# 6502_Based_Board.net
KiCad netlist of a schematic drawn in EAGLE
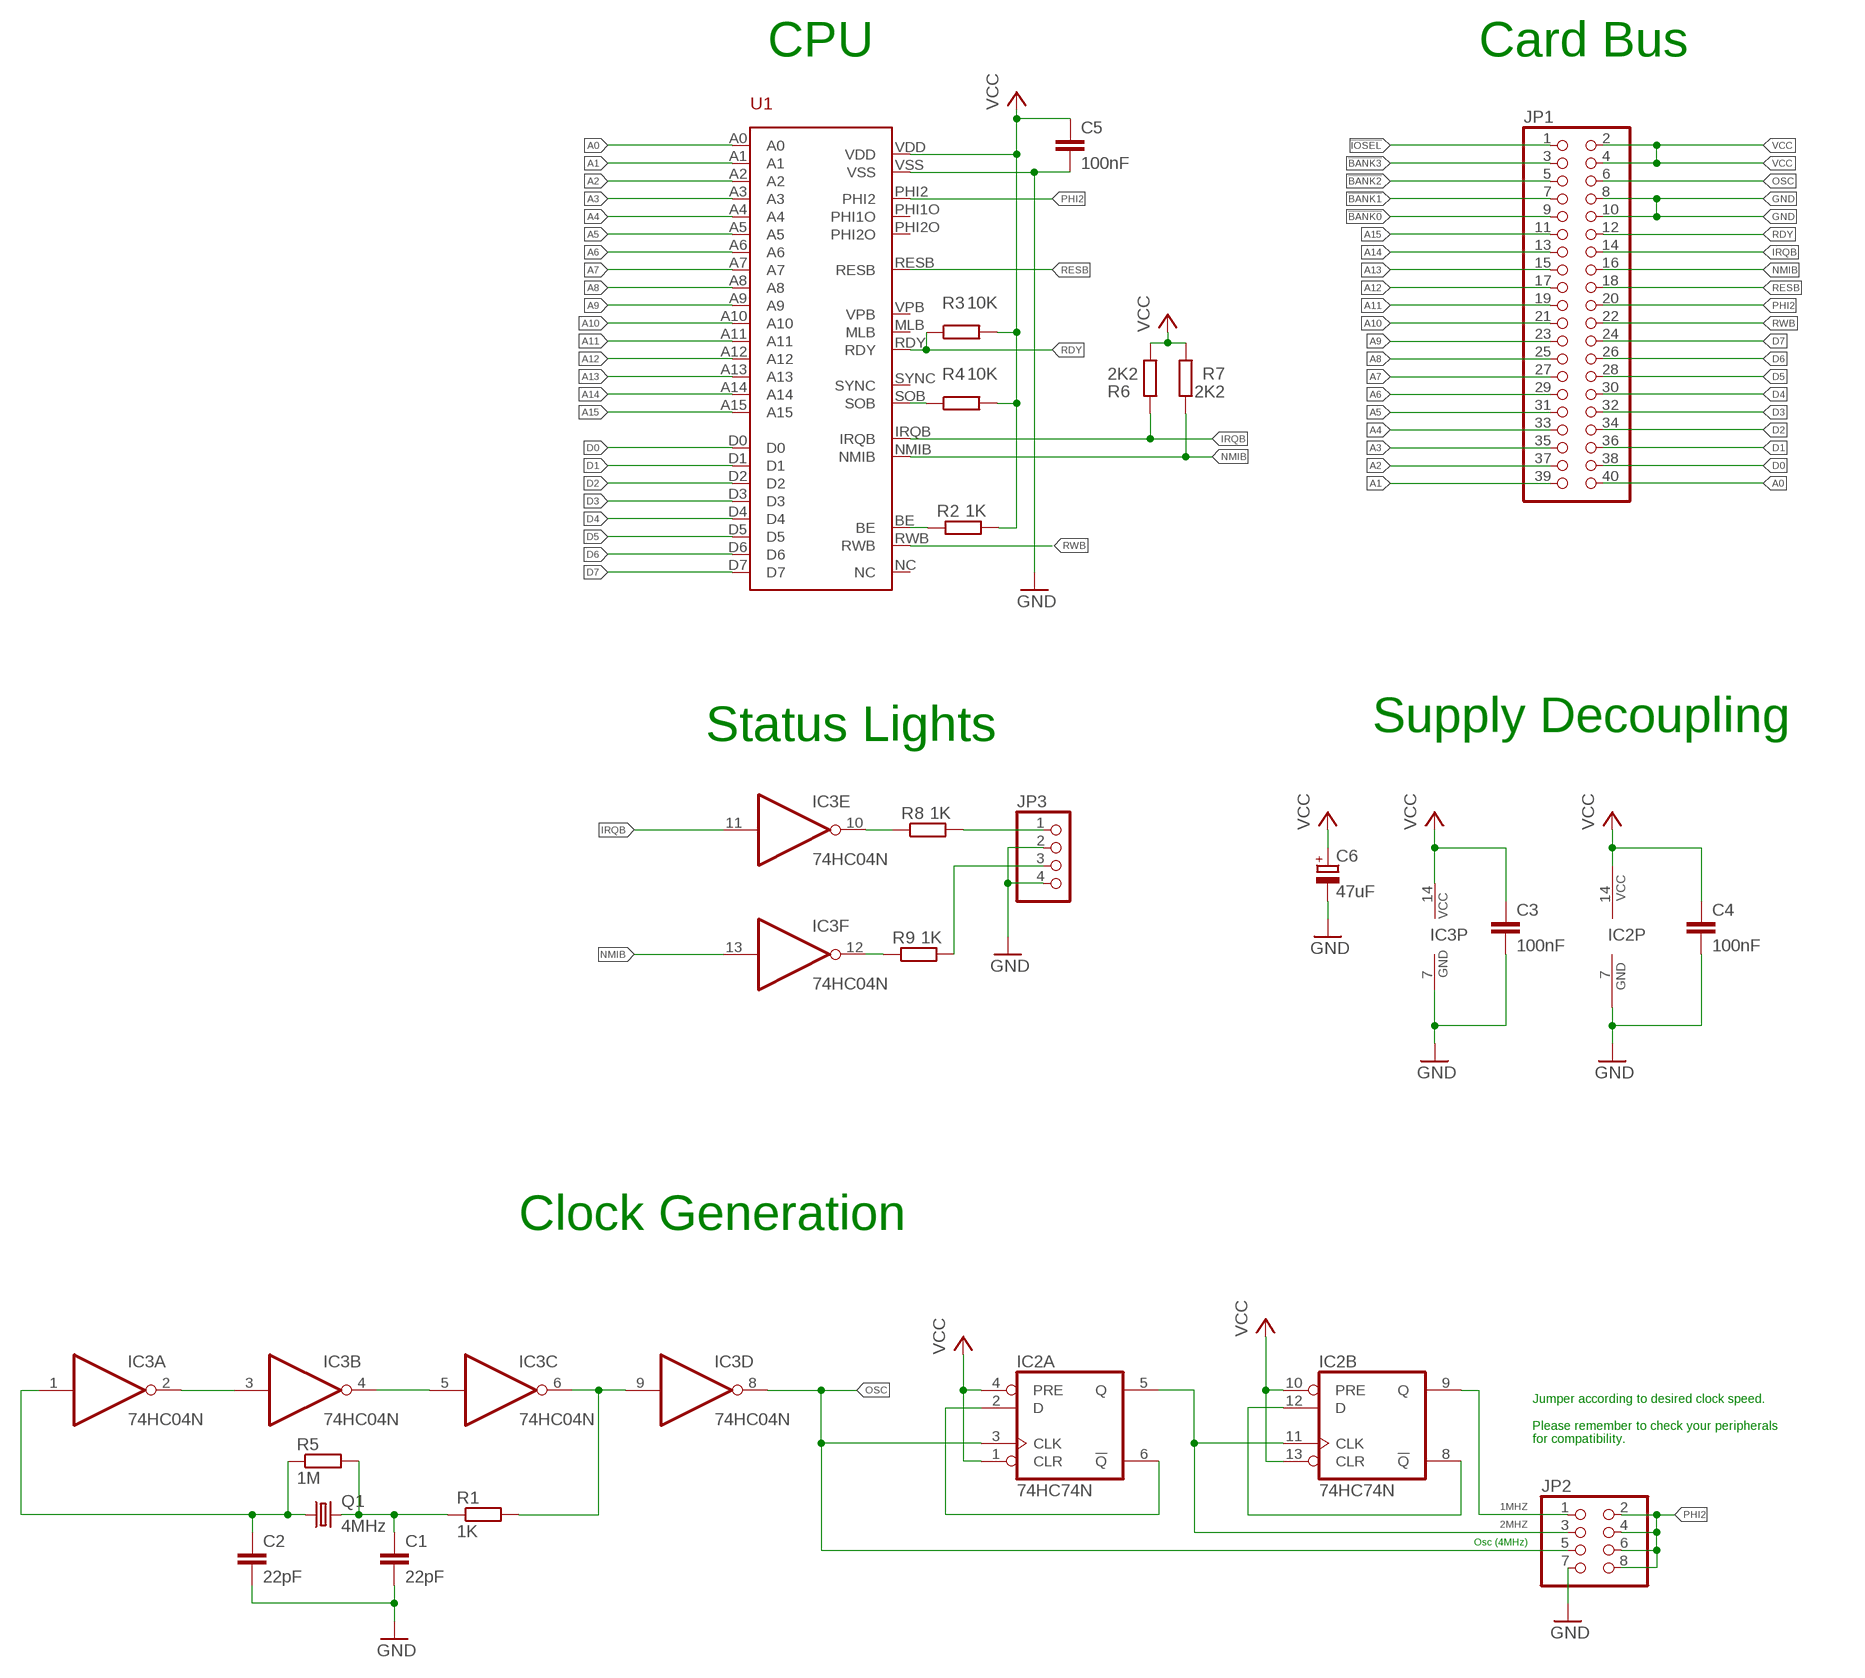
[diagram p0: schematic, sheet 1]

(export (version "E")
  (design (tool "Eeschema 10.0.6"))
  (components
    (comp (ref "C1")
      (value "22pF")
      (footprint "eagle-import:C050-025X075")
      (libsource (lib "eagle-import") (part "C-EU050-025X075"))
    )
    (comp (ref "C2")
      (value "22pF")
      (footprint "eagle-import:C050-025X075")
      (libsource (lib "eagle-import") (part "C-EU050-025X075"))
    )
    (comp (ref "C3")
      (value "100nF")
      (footprint "eagle-import:C050-025X075")
      (libsource (lib "eagle-import") (part "C-EU050-025X075"))
    )
    (comp (ref "C4")
      (value "100nF")
      (footprint "eagle-import:C050-025X075")
      (libsource (lib "eagle-import") (part "C-EU050-025X075"))
    )
    (comp (ref "C5")
      (value "100nF")
      (footprint "eagle-import:C050-025X075")
      (libsource (lib "eagle-import") (part "C-EU050-025X075"))
    )
    (comp (ref "C6")
      (value "47uF")
      (footprint "eagle-import:E2,5-7")
      (libsource (lib "eagle-import") (part "CPOL-EUE2.5-7"))
    )
    (comp (ref "IC2")
      (value "74HC74N")
      (footprint "eagle-import:DIL14")
      (libsource (lib "eagle-import") (part "7474NLS"))
    )
    (comp (ref "IC3")
      (value "74HC04N")
      (footprint "eagle-import:DIL14")
      (libsource (lib "eagle-import") (part "7404NHC"))
    )
    (comp (ref "JP1")
      (value "PINHD-2X20/90")
      (footprint "eagle-import:2X20_90")
      (libsource (lib "eagle-import") (part "PINHD-2X20/90"))
    )
    (comp (ref "JP2")
      (value "PINHD-2X4")
      (footprint "eagle-import:2X04")
      (libsource (lib "eagle-import") (part "PINHD-2X4"))
    )
    (comp (ref "JP3")
      (value "PINHD-1X4/90")
      (footprint "eagle-import:1X04_90")
      (libsource (lib "eagle-import") (part "PINHD-1X4/90"))
    )
    (comp (ref "Q1")
      (value "4MHz")
      (footprint "eagle-import:HC49_S")
      (libsource (lib "eagle-import") (part "CRYSTALHC49S"))
    )
    (comp (ref "R1")
      (value "1K")
      (footprint "eagle-import:0207_2V")
      (libsource (lib "eagle-import") (part "R-EU_0207/2V"))
    )
    (comp (ref "R2")
      (value "1K")
      (footprint "eagle-import:0207_2V")
      (libsource (lib "eagle-import") (part "R-EU_0207/2V"))
    )
    (comp (ref "R3")
      (value "10K")
      (footprint "eagle-import:0207_2V")
      (libsource (lib "eagle-import") (part "R-EU_0207/2V"))
    )
    (comp (ref "R4")
      (value "10K")
      (footprint "eagle-import:0207_2V")
      (libsource (lib "eagle-import") (part "R-EU_0207/2V"))
    )
    (comp (ref "R5")
      (value "1M")
      (footprint "eagle-import:0207_2V")
      (libsource (lib "eagle-import") (part "R-EU_0207/2V"))
    )
    (comp (ref "R6")
      (value "2K2")
      (footprint "eagle-import:0207_10")
      (libsource (lib "eagle-import") (part "R-EU_0207/10"))
    )
    (comp (ref "R7")
      (value "2K2")
      (footprint "eagle-import:0207_10")
      (libsource (lib "eagle-import") (part "R-EU_0207/10"))
    )
    (comp (ref "R8")
      (value "1K")
      (footprint "eagle-import:0207_2V")
      (libsource (lib "eagle-import") (part "R-EU_0207/2V"))
    )
    (comp (ref "R9")
      (value "1K")
      (footprint "eagle-import:0207_2V")
      (libsource (lib "eagle-import") (part "R-EU_0207/2V"))
    )
    (comp (ref "U1")
      (value "W65C02S-DIP")
      (footprint "eagle-import:DIP40")
      (libsource (lib "eagle-import") (part "W65C02S-DIP"))
    )
  )
  (nets
    (net (code "1") (name "/1MHZ") (class "Default")
      (node (ref "IC2") (pin "9") (pinfunction "Q_9") (pintype "output"))
      (node (ref "JP2") (pin "1") (pinfunction "1_1") (pintype "passive"))
    )
    (net (code "2") (name "/2MHZ") (class "Default")
      (node (ref "IC2") (pin "11") (pinfunction "CLK_11") (pintype "input"))
      (node (ref "IC2") (pin "5") (pinfunction "Q_5") (pintype "output"))
      (node (ref "JP2") (pin "3") (pinfunction "3_3") (pintype "passive"))
    )
    (net (code "3") (name "/~{BANK0}") (class "Default")
      (node (ref "JP1") (pin "9") (pinfunction "9_9") (pintype "passive"))
    )
    (net (code "4") (name "/~{BANK1}") (class "Default")
      (node (ref "JP1") (pin "7") (pinfunction "7_7") (pintype "passive"))
    )
    (net (code "5") (name "/~{BANK2}") (class "Default")
      (node (ref "JP1") (pin "5") (pinfunction "5_5") (pintype "passive"))
    )
    (net (code "6") (name "/~{BANK3}") (class "Default")
      (node (ref "JP1") (pin "3") (pinfunction "3_3") (pintype "passive"))
    )
    (net (code "7") (name "/~{IOSEL}") (class "Default")
      (node (ref "JP1") (pin "1") (pinfunction "1_1") (pintype "passive"))
    )
    (net (code "8") (name "A0") (class "Default")
      (node (ref "JP1") (pin "40") (pinfunction "40_40") (pintype "passive"))
      (node (ref "U1") (pin "A0") (pinfunction "A0_A0") (pintype "output"))
    )
    (net (code "9") (name "A1") (class "Default")
      (node (ref "JP1") (pin "39") (pinfunction "39_39") (pintype "passive"))
      (node (ref "U1") (pin "A1") (pinfunction "A1_A1") (pintype "output"))
    )
    (net (code "10") (name "A2") (class "Default")
      (node (ref "JP1") (pin "37") (pinfunction "37_37") (pintype "passive"))
      (node (ref "U1") (pin "A2") (pinfunction "A2_A2") (pintype "output"))
    )
    (net (code "11") (name "A3") (class "Default")
      (node (ref "JP1") (pin "35") (pinfunction "35_35") (pintype "passive"))
      (node (ref "U1") (pin "A3") (pinfunction "A3_A3") (pintype "output"))
    )
    (net (code "12") (name "A4") (class "Default")
      (node (ref "JP1") (pin "33") (pinfunction "33_33") (pintype "passive"))
      (node (ref "U1") (pin "A4") (pinfunction "A4_A4") (pintype "output"))
    )
    (net (code "13") (name "A5") (class "Default")
      (node (ref "JP1") (pin "31") (pinfunction "31_31") (pintype "passive"))
      (node (ref "U1") (pin "A5") (pinfunction "A5_A5") (pintype "output"))
    )
    (net (code "14") (name "A6") (class "Default")
      (node (ref "JP1") (pin "29") (pinfunction "29_29") (pintype "passive"))
      (node (ref "U1") (pin "A6") (pinfunction "A6_A6") (pintype "output"))
    )
    (net (code "15") (name "A7") (class "Default")
      (node (ref "JP1") (pin "27") (pinfunction "27_27") (pintype "passive"))
      (node (ref "U1") (pin "A7") (pinfunction "A7_A7") (pintype "output"))
    )
    (net (code "16") (name "A8") (class "Default")
      (node (ref "JP1") (pin "25") (pinfunction "25_25") (pintype "passive"))
      (node (ref "U1") (pin "A8") (pinfunction "A8_A8") (pintype "output"))
    )
    (net (code "17") (name "A9") (class "Default")
      (node (ref "JP1") (pin "23") (pinfunction "23_23") (pintype "passive"))
      (node (ref "U1") (pin "A9") (pinfunction "A9_A9") (pintype "output"))
    )
    (net (code "18") (name "A10") (class "Default")
      (node (ref "JP1") (pin "21") (pinfunction "21_21") (pintype "passive"))
      (node (ref "U1") (pin "A10") (pinfunction "A10_A10") (pintype "output"))
    )
    (net (code "19") (name "A11") (class "Default")
      (node (ref "JP1") (pin "19") (pinfunction "19_19") (pintype "passive"))
      (node (ref "U1") (pin "A11") (pinfunction "A11_A11") (pintype "output"))
    )
    (net (code "20") (name "A12") (class "Default")
      (node (ref "JP1") (pin "17") (pinfunction "17_17") (pintype "passive"))
      (node (ref "U1") (pin "A12") (pinfunction "A12_A12") (pintype "output"))
    )
    (net (code "21") (name "A13") (class "Default")
      (node (ref "JP1") (pin "15") (pinfunction "15_15") (pintype "passive"))
      (node (ref "U1") (pin "A13") (pinfunction "A13_A13") (pintype "output"))
    )
    (net (code "22") (name "A14") (class "Default")
      (node (ref "JP1") (pin "13") (pinfunction "13_13") (pintype "passive"))
      (node (ref "U1") (pin "A14") (pinfunction "A14_A14") (pintype "output"))
    )
    (net (code "23") (name "A15") (class "Default")
      (node (ref "JP1") (pin "11") (pinfunction "11_11") (pintype "passive"))
      (node (ref "U1") (pin "A15") (pinfunction "A15_A15") (pintype "output"))
    )
    (net (code "24") (name "D0") (class "Default")
      (node (ref "JP1") (pin "38") (pinfunction "38_38") (pintype "passive"))
      (node (ref "U1") (pin "D0") (pinfunction "D0_D0") (pintype "bidirectional"))
    )
    (net (code "25") (name "D1") (class "Default")
      (node (ref "JP1") (pin "36") (pinfunction "36_36") (pintype "passive"))
      (node (ref "U1") (pin "D1") (pinfunction "D1_D1") (pintype "bidirectional"))
    )
    (net (code "26") (name "D2") (class "Default")
      (node (ref "JP1") (pin "34") (pinfunction "34_34") (pintype "passive"))
      (node (ref "U1") (pin "D2") (pinfunction "D2_D2") (pintype "bidirectional"))
    )
    (net (code "27") (name "D3") (class "Default")
      (node (ref "JP1") (pin "32") (pinfunction "32_32") (pintype "passive"))
      (node (ref "U1") (pin "D3") (pinfunction "D3_D3") (pintype "bidirectional"))
    )
    (net (code "28") (name "D4") (class "Default")
      (node (ref "JP1") (pin "30") (pinfunction "30_30") (pintype "passive"))
      (node (ref "U1") (pin "D4") (pinfunction "D4_D4") (pintype "bidirectional"))
    )
    (net (code "29") (name "D5") (class "Default")
      (node (ref "JP1") (pin "28") (pinfunction "28_28") (pintype "passive"))
      (node (ref "U1") (pin "D5") (pinfunction "D5_D5") (pintype "bidirectional"))
    )
    (net (code "30") (name "D6") (class "Default")
      (node (ref "JP1") (pin "26") (pinfunction "26_26") (pintype "passive"))
      (node (ref "U1") (pin "D6") (pinfunction "D6_D6") (pintype "bidirectional"))
    )
    (net (code "31") (name "D7") (class "Default")
      (node (ref "JP1") (pin "24") (pinfunction "24_24") (pintype "passive"))
      (node (ref "U1") (pin "D7") (pinfunction "D7_D7") (pintype "bidirectional"))
    )
    (net (code "32") (name "GND") (class "Default")
      (node (ref "C1") (pin "2") (pinfunction "2_2") (pintype "passive"))
      (node (ref "C2") (pin "2") (pinfunction "2_2") (pintype "passive"))
      (node (ref "C3") (pin "2") (pinfunction "2_2") (pintype "passive"))
      (node (ref "C4") (pin "2") (pinfunction "2_2") (pintype "passive"))
      (node (ref "C5") (pin "2") (pinfunction "2_2") (pintype "passive"))
      (node (ref "C6") (pin "-") (pinfunction "-_-") (pintype "passive"))
      (node (ref "IC2") (pin "7") (pinfunction "GND_7") (pintype "power_in"))
      (node (ref "IC3") (pin "7") (pinfunction "GND_7") (pintype "power_in"))
      (node (ref "JP1") (pin "10") (pinfunction "10_10") (pintype "passive"))
      (node (ref "JP1") (pin "8") (pinfunction "8_8") (pintype "passive"))
      (node (ref "JP2") (pin "7") (pinfunction "7_7") (pintype "passive"))
      (node (ref "JP3") (pin "2") (pinfunction "2_2") (pintype "passive"))
      (node (ref "JP3") (pin "4") (pinfunction "4_4") (pintype "passive"))
      (node (ref "U1") (pin "VSS") (pinfunction "VSS_VSS") (pintype "power_in"))
    )
    (net (code "33") (name "IRQB") (class "Default")
      (node (ref "IC3") (pin "11") (pinfunction "I_11") (pintype "input"))
      (node (ref "JP1") (pin "14") (pinfunction "14_14") (pintype "passive"))
      (node (ref "R6") (pin "1") (pinfunction "1_1") (pintype "passive"))
      (node (ref "U1") (pin "IRQB") (pinfunction "IRQB_IRQB") (pintype "input"))
    )
    (net (code "34") (name "NMIB") (class "Default")
      (node (ref "IC3") (pin "13") (pinfunction "I_13") (pintype "input"))
      (node (ref "JP1") (pin "16") (pinfunction "16_16") (pintype "passive"))
      (node (ref "R7") (pin "1") (pinfunction "1_1") (pintype "passive"))
      (node (ref "U1") (pin "NMIB") (pinfunction "NMIB_NMIB") (pintype "input"))
    )
    (net (code "35") (name "Net-(C1-Pad1)") (class "Default")
      (node (ref "C1") (pin "1") (pinfunction "1_1") (pintype "passive"))
      (node (ref "Q1") (pin "2") (pinfunction "2_2") (pintype "passive"))
      (node (ref "R1") (pin "1") (pinfunction "1_1") (pintype "passive"))
      (node (ref "R5") (pin "2") (pinfunction "2_2") (pintype "passive"))
    )
    (net (code "36") (name "Net-(IC2A-D)") (class "Default")
      (node (ref "IC2") (pin "2") (pinfunction "D_2") (pintype "input"))
      (node (ref "IC2") (pin "6") (pinfunction "~{Q}_6") (pintype "output"))
    )
    (net (code "37") (name "Net-(IC2B-D)") (class "Default")
      (node (ref "IC2") (pin "12") (pinfunction "D_12") (pintype "input"))
      (node (ref "IC2") (pin "8") (pinfunction "~{Q}_8") (pintype "output"))
    )
    (net (code "38") (name "Net-(IC3A-I)") (class "Default")
      (node (ref "C2") (pin "1") (pinfunction "1_1") (pintype "passive"))
      (node (ref "IC3") (pin "1") (pinfunction "I_1") (pintype "input"))
      (node (ref "Q1") (pin "1") (pinfunction "1_1") (pintype "passive"))
      (node (ref "R5") (pin "1") (pinfunction "1_1") (pintype "passive"))
    )
    (net (code "39") (name "Net-(IC3A-O)") (class "Default")
      (node (ref "IC3") (pin "2") (pinfunction "O_2") (pintype "output"))
      (node (ref "IC3") (pin "3") (pinfunction "I_3") (pintype "input"))
    )
    (net (code "40") (name "Net-(IC3B-O)") (class "Default")
      (node (ref "IC3") (pin "4") (pinfunction "O_4") (pintype "output"))
      (node (ref "IC3") (pin "5") (pinfunction "I_5") (pintype "input"))
    )
    (net (code "41") (name "Net-(IC3C-O)") (class "Default")
      (node (ref "IC3") (pin "6") (pinfunction "O_6") (pintype "output"))
      (node (ref "IC3") (pin "9") (pinfunction "I_9") (pintype "input"))
      (node (ref "R1") (pin "2") (pinfunction "2_2") (pintype "passive"))
    )
    (net (code "42") (name "Net-(IC3E-O)") (class "Default")
      (node (ref "IC3") (pin "10") (pinfunction "O_10") (pintype "output"))
      (node (ref "R8") (pin "1") (pinfunction "1_1") (pintype "passive"))
    )
    (net (code "43") (name "Net-(IC3F-O)") (class "Default")
      (node (ref "IC3") (pin "12") (pinfunction "O_12") (pintype "output"))
      (node (ref "R9") (pin "1") (pinfunction "1_1") (pintype "passive"))
    )
    (net (code "44") (name "Net-(JP3-Pad1)") (class "Default")
      (node (ref "JP3") (pin "1") (pinfunction "1_1") (pintype "passive"))
      (node (ref "R8") (pin "2") (pinfunction "2_2") (pintype "passive"))
    )
    (net (code "45") (name "Net-(JP3-Pad3)") (class "Default")
      (node (ref "JP3") (pin "3") (pinfunction "3_3") (pintype "passive"))
      (node (ref "R9") (pin "2") (pinfunction "2_2") (pintype "passive"))
    )
    (net (code "46") (name "Net-(R2-Pad1)") (class "Default")
      (node (ref "R2") (pin "1") (pinfunction "1_1") (pintype "passive"))
      (node (ref "U1") (pin "BE") (pinfunction "BE_BE") (pintype "input"))
    )
    (net (code "47") (name "Net-(R4-Pad1)") (class "Default")
      (node (ref "R4") (pin "1") (pinfunction "1_1") (pintype "passive"))
      (node (ref "U1") (pin "SOB") (pinfunction "SOB_SOB") (pintype "input"))
    )
    (net (code "48") (name "OSC") (class "Default")
      (node (ref "IC2") (pin "3") (pinfunction "CLK_3") (pintype "input"))
      (node (ref "IC3") (pin "8") (pinfunction "O_8") (pintype "output"))
      (node (ref "JP1") (pin "6") (pinfunction "6_6") (pintype "passive"))
      (node (ref "JP2") (pin "5") (pinfunction "5_5") (pintype "passive"))
    )
    (net (code "49") (name "PHI2") (class "Default")
      (node (ref "JP1") (pin "20") (pinfunction "20_20") (pintype "passive"))
      (node (ref "JP2") (pin "2") (pinfunction "2_2") (pintype "passive"))
      (node (ref "JP2") (pin "4") (pinfunction "4_4") (pintype "passive"))
      (node (ref "JP2") (pin "6") (pinfunction "6_6") (pintype "passive"))
      (node (ref "JP2") (pin "8") (pinfunction "8_8") (pintype "passive"))
      (node (ref "U1") (pin "PHI2") (pinfunction "PHI2_PHI2") (pintype "input"))
    )
    (net (code "50") (name "RDY") (class "Default")
      (node (ref "JP1") (pin "12") (pinfunction "12_12") (pintype "passive"))
      (node (ref "R3") (pin "1") (pinfunction "1_1") (pintype "passive"))
      (node (ref "U1") (pin "RDY") (pinfunction "RDY_RDY") (pintype "input"))
    )
    (net (code "51") (name "RESB") (class "Default")
      (node (ref "JP1") (pin "18") (pinfunction "18_18") (pintype "passive"))
      (node (ref "U1") (pin "RESB") (pinfunction "RESB_RESB") (pintype "input"))
    )
    (net (code "52") (name "RWB") (class "Default")
      (node (ref "JP1") (pin "22") (pinfunction "22_22") (pintype "passive"))
      (node (ref "U1") (pin "RWB") (pinfunction "RWB_RWB") (pintype "output"))
    )
    (net (code "53") (name "VCC") (class "Default")
      (node (ref "C3") (pin "1") (pinfunction "1_1") (pintype "passive"))
      (node (ref "C4") (pin "1") (pinfunction "1_1") (pintype "passive"))
      (node (ref "C5") (pin "1") (pinfunction "1_1") (pintype "passive"))
      (node (ref "C6") (pin "+") (pinfunction "+_+") (pintype "passive"))
      (node (ref "IC2") (pin "1") (pinfunction "CLR_1") (pintype "input"))
      (node (ref "IC2") (pin "10") (pinfunction "PRE_10") (pintype "input"))
      (node (ref "IC2") (pin "13") (pinfunction "CLR_13") (pintype "input"))
      (node (ref "IC2") (pin "14") (pinfunction "VCC_14") (pintype "power_in"))
      (node (ref "IC2") (pin "4") (pinfunction "PRE_4") (pintype "input"))
      (node (ref "IC3") (pin "14") (pinfunction "VCC_14") (pintype "power_in"))
      (node (ref "JP1") (pin "2") (pinfunction "2_2") (pintype "passive"))
      (node (ref "JP1") (pin "4") (pinfunction "4_4") (pintype "passive"))
      (node (ref "R2") (pin "2") (pinfunction "2_2") (pintype "passive"))
      (node (ref "R3") (pin "2") (pinfunction "2_2") (pintype "passive"))
      (node (ref "R4") (pin "2") (pinfunction "2_2") (pintype "passive"))
      (node (ref "R6") (pin "2") (pinfunction "2_2") (pintype "passive"))
      (node (ref "R7") (pin "2") (pinfunction "2_2") (pintype "passive"))
      (node (ref "U1") (pin "VDD") (pinfunction "VDD_VDD") (pintype "power_in"))
    )
    (net (code "54") (name "unconnected-(U1-PadMLB)") (class "Default")
      (node (ref "U1") (pin "MLB") (pinfunction "MLB_MLB") (pintype "output"))
    )
    (net (code "55") (name "unconnected-(U1-PadNC)") (class "Default")
      (node (ref "U1") (pin "NC") (pinfunction "NC_NC") (pintype "bidirectional"))
    )
    (net (code "56") (name "unconnected-(U1-PadPHI1O)") (class "Default")
      (node (ref "U1") (pin "PHI1O") (pinfunction "PHI1O_PHI1O") (pintype "output"))
    )
    (net (code "57") (name "unconnected-(U1-PadPHI2O)") (class "Default")
      (node (ref "U1") (pin "PHI2O") (pinfunction "PHI2O_PHI2O") (pintype "output"))
    )
    (net (code "58") (name "unconnected-(U1-PadSYNC)") (class "Default")
      (node (ref "U1") (pin "SYNC") (pinfunction "SYNC_SYNC") (pintype "output"))
    )
    (net (code "59") (name "unconnected-(U1-PadVPB)") (class "Default")
      (node (ref "U1") (pin "VPB") (pinfunction "VPB_VPB") (pintype "output"))
    )
  )
)
